# CPU.net
KiCad netlist of a schematic drawn in Altium Designer
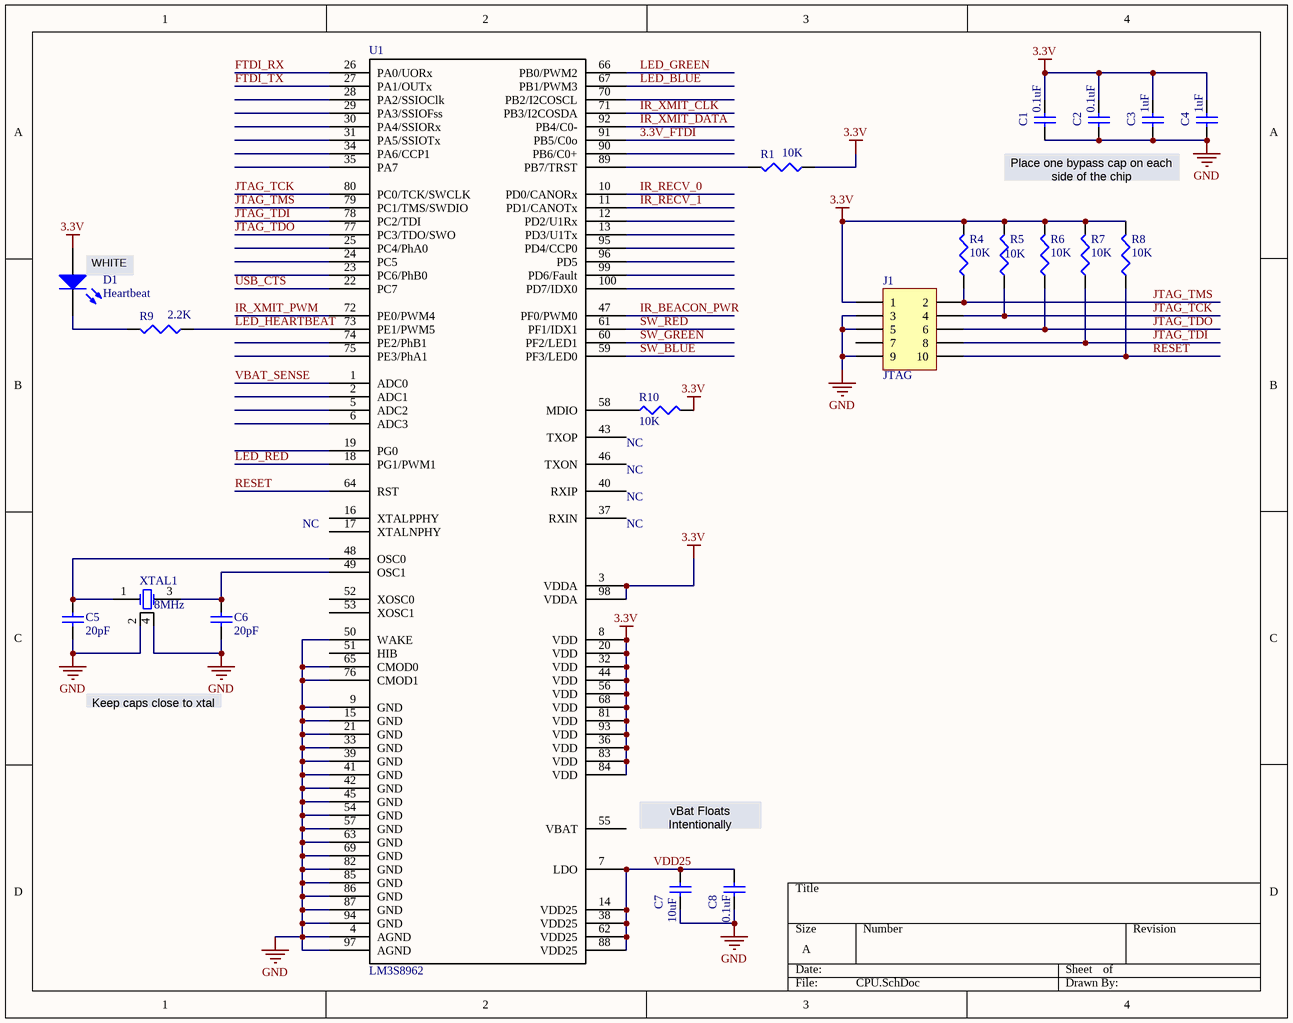
[diagram p0: CPU.SchDoc]

(export (version "E")
  (design (tool "Eeschema 10.0.6"))
  (components
    (comp (ref "C1")
      (value "0.1uF")
      (footprint "0402")
      (description "Capacitor (Semiconductor SIM Model)")
      (fields (field (name "Comment") "Cap Semi") (field (name "PUBLISHER") "Altium Limited"))
      (libsource (lib "Miscellaneous Devices") (part "Cap Semi"))
    )
    (comp (ref "C2")
      (value "0.1uF")
      (footprint "0402")
      (description "Capacitor (Semiconductor SIM Model)")
      (fields (field (name "Comment") "Cap Semi") (field (name "PUBLISHER") "Altium Limited"))
      (libsource (lib "Miscellaneous Devices") (part "Cap Semi"))
    )
    (comp (ref "C3")
      (value "1uF")
      (footprint "1608[0603]")
      (description "Capacitor (Semiconductor SIM Model)")
      (fields (field (name "Comment") "Cap Semi") (field (name "PUBLISHER") "Altium Limited"))
      (libsource (lib "Miscellaneous Devices") (part "Cap Semi"))
    )
    (comp (ref "C4")
      (value "1uF")
      (footprint "1608[0603]")
      (description "Capacitor (Semiconductor SIM Model)")
      (fields (field (name "Comment") "Cap Semi") (field (name "PUBLISHER") "Altium Limited"))
      (libsource (lib "Miscellaneous Devices") (part "Cap Semi"))
    )
    (comp (ref "C5")
      (value "20pF")
      (footprint "0402")
      (description "Capacitor (Semiconductor SIM Model)")
      (fields (field (name "Comment") "Cap Semi") (field (name "PUBLISHER") "Altium Limited"))
      (libsource (lib "Miscellaneous Devices") (part "Cap Semi"))
    )
    (comp (ref "C6")
      (value "20pF")
      (footprint "0402")
      (description "Capacitor (Semiconductor SIM Model)")
      (fields (field (name "Comment") "Cap Semi") (field (name "PUBLISHER") "Altium Limited"))
      (libsource (lib "Miscellaneous Devices") (part "Cap Semi"))
    )
    (comp (ref "C7")
      (value "10uF")
      (footprint "1608[0603]")
      (description "Capacitor (Semiconductor SIM Model)")
      (fields (field (name "Comment") "Cap Semi") (field (name "PUBLISHER") "Altium Limited"))
      (libsource (lib "Miscellaneous Devices") (part "Cap Semi"))
    )
    (comp (ref "C8")
      (value "0.1uF")
      (footprint "0402")
      (description "Capacitor (Semiconductor SIM Model)")
      (fields (field (name "Comment") "Cap Semi") (field (name "PUBLISHER") "Altium Limited"))
      (libsource (lib "Miscellaneous Devices") (part "Cap Semi"))
    )
    (comp (ref "D1")
      (value "Heartbeat")
      (footprint "SurfaceMount(603)")
      (libsource (lib "mrone") (part "LED"))
    )
    (comp (ref "J1")
      (value "JTAG")
      (footprint "JTAG-10")
      (description "Header, 5-Pin, Dual row, Right Angle")
      (fields (field (name "PUBLISHER") "Altium Limited"))
      (libsource (lib "Miscellaneous Connectors") (part "Header 5X2H"))
    )
    (comp (ref "R1")
      (value "10K")
      (footprint "J1-0603")
      (description "Resistor")
      (fields (field (name "Comment") "Res3") (field (name "PUBLISHER") "Altium Limited"))
      (libsource (lib "Miscellaneous Devices") (part "Res3"))
    )
    (comp (ref "R4")
      (value "10K")
      (footprint "J1-0603")
      (description "Resistor")
      (fields (field (name "Comment") "Res3") (field (name "PUBLISHER") "Altium Limited"))
      (libsource (lib "Miscellaneous Devices") (part "Res3"))
    )
    (comp (ref "R5")
      (value "10K")
      (footprint "J1-0603")
      (description "Resistor")
      (fields (field (name "Comment") "Res3") (field (name "PUBLISHER") "Altium Limited"))
      (libsource (lib "Miscellaneous Devices") (part "Res3"))
    )
    (comp (ref "R6")
      (value "10K")
      (footprint "J1-0603")
      (description "Resistor")
      (fields (field (name "Comment") "Res3") (field (name "PUBLISHER") "Altium Limited"))
      (libsource (lib "Miscellaneous Devices") (part "Res3"))
    )
    (comp (ref "R7")
      (value "10K")
      (footprint "J1-0603")
      (description "Resistor")
      (fields (field (name "Comment") "Res3") (field (name "PUBLISHER") "Altium Limited"))
      (libsource (lib "Miscellaneous Devices") (part "Res3"))
    )
    (comp (ref "R8")
      (value "10K")
      (footprint "J1-0603")
      (description "Resistor")
      (fields (field (name "Comment") "Res3") (field (name "PUBLISHER") "Altium Limited"))
      (libsource (lib "Miscellaneous Devices") (part "Res3"))
    )
    (comp (ref "R9")
      (value "2.2K")
      (footprint "J1-0603")
      (description "Resistor")
      (fields (field (name "Comment") "Res3") (field (name "PUBLISHER") "Altium Limited"))
      (libsource (lib "Miscellaneous Devices") (part "Res3"))
    )
    (comp (ref "R10")
      (value "10K")
      (footprint "J1-0603")
      (description "Resistor")
      (fields (field (name "Comment") "Res3") (field (name "PUBLISHER") "Altium Limited"))
      (libsource (lib "Miscellaneous Devices") (part "Res3"))
    )
    (comp (ref "U1")
      (value "LM3S8962")
      (footprint "LQFP-100")
      (libsource (lib "Schematic Components") (part "LM3S8962"))
    )
    (comp (ref "XTAL1") (value "8MHz") (footprint "CRYSTAL") (libsource (lib "mrone") (part "Crystal")))
  )
  (nets
    (net (code "1") (name "/3.3V_FTDI") (class "Default")
      (node (ref "U1") (pin "91") (pinfunction "PB5/C0o_91") (pintype "passive"))
    )
    (net (code "3") (name "/FTDI_RX") (class "Default")
      (node (ref "U1") (pin "26") (pinfunction "PA0/UORx_26") (pintype "passive"))
    )
    (net (code "4") (name "/FTDI_TX") (class "Default")
      (node (ref "U1") (pin "27") (pinfunction "PA1/OUTx_27") (pintype "passive"))
    )
    (net (code "5") (name "/IR_BEACON_PWR") (class "Default")
      (node (ref "U1") (pin "47") (pinfunction "PF0/PWM0_47") (pintype "passive"))
    )
    (net (code "6") (name "/IR_RECV_0") (class "Default")
      (node (ref "U1") (pin "10") (pinfunction "PD0/CANORx_10") (pintype "passive"))
    )
    (net (code "7") (name "/IR_RECV_1") (class "Default")
      (node (ref "U1") (pin "11") (pinfunction "PD1/CANOTx_11") (pintype "passive"))
    )
    (net (code "8") (name "/IR_XMIT_CLK") (class "Default")
      (node (ref "U1") (pin "71") (pinfunction "PB3/I2COSDA_71") (pintype "passive"))
    )
    (net (code "9") (name "/IR_XMIT_DATA") (class "Default")
      (node (ref "U1") (pin "92") (pinfunction "PB4/C0-_92") (pintype "passive"))
    )
    (net (code "10") (name "/IR_XMIT_PWM") (class "Default")
      (node (ref "U1") (pin "72") (pinfunction "PE0/PWM4_72") (pintype "passive"))
    )
    (net (code "11") (name "/JTAG_TCK") (class "Default")
      (node (ref "J1") (pin "4") (pinfunction "4_4") (pintype "passive"))
      (node (ref "R5") (pin "1") (pinfunction "1_1") (pintype "passive"))
      (node (ref "U1") (pin "80") (pinfunction "PC0/TCK/SWCLK_80") (pintype "passive"))
    )
    (net (code "12") (name "/JTAG_TDI") (class "Default")
      (node (ref "J1") (pin "8") (pinfunction "8_8") (pintype "passive"))
      (node (ref "R7") (pin "1") (pinfunction "1_1") (pintype "passive"))
      (node (ref "U1") (pin "78") (pinfunction "PC2/TDI_78") (pintype "passive"))
    )
    (net (code "13") (name "/JTAG_TDO") (class "Default")
      (node (ref "J1") (pin "6") (pinfunction "6_6") (pintype "passive"))
      (node (ref "R6") (pin "1") (pinfunction "1_1") (pintype "passive"))
      (node (ref "U1") (pin "77") (pinfunction "PC3/TDO/SWO_77") (pintype "passive"))
    )
    (net (code "14") (name "/JTAG_TMS") (class "Default")
      (node (ref "J1") (pin "2") (pinfunction "2_2") (pintype "passive"))
      (node (ref "R4") (pin "1") (pinfunction "1_1") (pintype "passive"))
      (node (ref "U1") (pin "79") (pinfunction "PC1/TMS/SWDIO_79") (pintype "passive"))
    )
    (net (code "15") (name "/LED_BLUE") (class "Default")
      (node (ref "U1") (pin "67") (pinfunction "PB1/PWM3_67") (pintype "passive"))
    )
    (net (code "16") (name "/LED_GREEN") (class "Default")
      (node (ref "U1") (pin "66") (pinfunction "PB0/PWM2_66") (pintype "passive"))
    )
    (net (code "17") (name "/LED_HEARTBEAT") (class "Default")
      (node (ref "R9") (pin "1") (pinfunction "1_1") (pintype "passive"))
      (node (ref "U1") (pin "73") (pinfunction "PE1/PWM5_73") (pintype "passive"))
    )
    (net (code "18") (name "/LED_RED") (class "Default")
      (node (ref "U1") (pin "18") (pinfunction "PG1/PWM1_18") (pintype "passive"))
    )
    (net (code "19") (name "/RESET") (class "Default")
      (node (ref "J1") (pin "10") (pinfunction "10_10") (pintype "passive"))
      (node (ref "R8") (pin "1") (pinfunction "1_1") (pintype "passive"))
      (node (ref "U1") (pin "64") (pinfunction "RST_64") (pintype "passive"))
    )
    (net (code "20") (name "/SW_BLUE") (class "Default")
      (node (ref "U1") (pin "59") (pinfunction "PF3/LED0_59") (pintype "passive"))
    )
    (net (code "21") (name "/SW_GREEN") (class "Default")
      (node (ref "U1") (pin "60") (pinfunction "PF2/LED1_60") (pintype "passive"))
    )
    (net (code "22") (name "/SW_RED") (class "Default")
      (node (ref "U1") (pin "61") (pinfunction "PF1/IDX1_61") (pintype "passive"))
    )
    (net (code "23") (name "/USB_CTS") (class "Default")
      (node (ref "U1") (pin "22") (pinfunction "PC7_22") (pintype "passive"))
    )
    (net (code "24") (name "/VBAT_SENSE") (class "Default")
      (node (ref "U1") (pin "1") (pinfunction "ADC0_1") (pintype "passive"))
    )
    (net (code "25") (name "/VDD25") (class "Default")
      (node (ref "C7") (pin "2") (pinfunction "2_2") (pintype "passive"))
      (node (ref "C8") (pin "2") (pinfunction "2_2") (pintype "passive"))
      (node (ref "U1") (pin "14") (pinfunction "VDD25_14") (pintype "passive"))
      (node (ref "U1") (pin "38") (pinfunction "VDD25_38") (pintype "passive"))
      (node (ref "U1") (pin "62") (pinfunction "VDD25_62") (pintype "passive"))
      (node (ref "U1") (pin "7") (pinfunction "LDO_7") (pintype "passive"))
      (node (ref "U1") (pin "88") (pinfunction "VDD25_88") (pintype "passive"))
    )
    (net (code "26") (name "3.3V") (class "Default")
      (node (ref "C1") (pin "2") (pinfunction "2_2") (pintype "passive"))
      (node (ref "C2") (pin "2") (pinfunction "2_2") (pintype "passive"))
      (node (ref "C3") (pin "2") (pinfunction "2_2") (pintype "passive"))
      (node (ref "C4") (pin "2") (pinfunction "2_2") (pintype "passive"))
      (node (ref "D1") (pin "1") (pinfunction "A_1") (pintype "passive"))
      (node (ref "J1") (pin "1") (pinfunction "1_1") (pintype "passive"))
      (node (ref "R1") (pin "1") (pinfunction "1_1") (pintype "passive"))
      (node (ref "R10") (pin "2") (pinfunction "2_2") (pintype "passive"))
      (node (ref "R4") (pin "2") (pinfunction "2_2") (pintype "passive"))
      (node (ref "R5") (pin "2") (pinfunction "2_2") (pintype "passive"))
      (node (ref "R6") (pin "2") (pinfunction "2_2") (pintype "passive"))
      (node (ref "R7") (pin "2") (pinfunction "2_2") (pintype "passive"))
      (node (ref "R8") (pin "2") (pinfunction "2_2") (pintype "passive"))
      (node (ref "U1") (pin "20") (pinfunction "VDD_20") (pintype "passive"))
      (node (ref "U1") (pin "3") (pinfunction "VDDA_3") (pintype "passive"))
      (node (ref "U1") (pin "32") (pinfunction "VDD_32") (pintype "passive"))
      (node (ref "U1") (pin "36") (pinfunction "VDD_36") (pintype "passive"))
      (node (ref "U1") (pin "44") (pinfunction "VDD_44") (pintype "passive"))
      (node (ref "U1") (pin "56") (pinfunction "VDD_56") (pintype "passive"))
      (node (ref "U1") (pin "68") (pinfunction "VDD_68") (pintype "passive"))
      (node (ref "U1") (pin "8") (pinfunction "VDD_8") (pintype "passive"))
      (node (ref "U1") (pin "81") (pinfunction "VDD_81") (pintype "passive"))
      (node (ref "U1") (pin "83") (pinfunction "VDD_83") (pintype "passive"))
      (node (ref "U1") (pin "84") (pinfunction "VDD_84") (pintype "passive"))
      (node (ref "U1") (pin "93") (pinfunction "VDD_93") (pintype "passive"))
      (node (ref "U1") (pin "98") (pinfunction "VDDA_98") (pintype "passive"))
    )
    (net (code "27") (name "GND") (class "Default")
      (node (ref "C1") (pin "1") (pinfunction "1_1") (pintype "passive"))
      (node (ref "C2") (pin "1") (pinfunction "1_1") (pintype "passive"))
      (node (ref "C3") (pin "1") (pinfunction "1_1") (pintype "passive"))
      (node (ref "C4") (pin "1") (pinfunction "1_1") (pintype "passive"))
      (node (ref "C5") (pin "1") (pinfunction "1_1") (pintype "passive"))
      (node (ref "C6") (pin "1") (pinfunction "1_1") (pintype "passive"))
      (node (ref "C7") (pin "1") (pinfunction "1_1") (pintype "passive"))
      (node (ref "C8") (pin "1") (pinfunction "1_1") (pintype "passive"))
      (node (ref "J1") (pin "3") (pinfunction "3_3") (pintype "passive"))
      (node (ref "J1") (pin "5") (pinfunction "5_5") (pintype "passive"))
      (node (ref "J1") (pin "9") (pinfunction "9_9") (pintype "passive"))
      (node (ref "U1") (pin "15") (pinfunction "GND_15") (pintype "passive"))
      (node (ref "U1") (pin "21") (pinfunction "GND_21") (pintype "passive"))
      (node (ref "U1") (pin "33") (pinfunction "GND_33") (pintype "passive"))
      (node (ref "U1") (pin "39") (pinfunction "GND_39") (pintype "passive"))
      (node (ref "U1") (pin "4") (pinfunction "AGND_4") (pintype "passive"))
      (node (ref "U1") (pin "41") (pinfunction "GND_41") (pintype "passive"))
      (node (ref "U1") (pin "42") (pinfunction "GND_42") (pintype "passive"))
      (node (ref "U1") (pin "45") (pinfunction "GND_45") (pintype "passive"))
      (node (ref "U1") (pin "50") (pinfunction "WAKE_50") (pintype "passive"))
      (node (ref "U1") (pin "54") (pinfunction "GND_54") (pintype "passive"))
      (node (ref "U1") (pin "57") (pinfunction "GND_57") (pintype "passive"))
      (node (ref "U1") (pin "63") (pinfunction "GND_63") (pintype "passive"))
      (node (ref "U1") (pin "65") (pinfunction "CMOD0_65") (pintype "passive"))
      (node (ref "U1") (pin "69") (pinfunction "GND_69") (pintype "passive"))
      (node (ref "U1") (pin "76") (pinfunction "CMOD1_76") (pintype "passive"))
      (node (ref "U1") (pin "82") (pinfunction "GND_82") (pintype "passive"))
      (node (ref "U1") (pin "85") (pinfunction "GND_85") (pintype "passive"))
      (node (ref "U1") (pin "86") (pinfunction "GND_86") (pintype "passive"))
      (node (ref "U1") (pin "87") (pinfunction "GND_87") (pintype "passive"))
      (node (ref "U1") (pin "9") (pinfunction "GND_9") (pintype "passive"))
      (node (ref "U1") (pin "94") (pinfunction "GND_94") (pintype "passive"))
      (node (ref "U1") (pin "97") (pinfunction "AGND_97") (pintype "passive"))
      (node (ref "XTAL1") (pin "2") (pinfunction "GND_2") (pintype "passive"))
      (node (ref "XTAL1") (pin "4") (pinfunction "GND_4") (pintype "passive"))
    )
    (net (code "28") (name "Net-(D1-K)") (class "Default")
      (node (ref "D1") (pin "2") (pinfunction "K_2") (pintype "passive"))
      (node (ref "R9") (pin "2") (pinfunction "2_2") (pintype "passive"))
    )
    (net (code "29") (name "Net-(U1-MDIO)") (class "Default")
      (node (ref "R10") (pin "1") (pinfunction "1_1") (pintype "passive"))
      (node (ref "U1") (pin "58") (pinfunction "MDIO_58") (pintype "passive"))
    )
    (net (code "30") (name "Net-(U1-OSC0)") (class "Default")
      (node (ref "C5") (pin "2") (pinfunction "2_2") (pintype "passive"))
      (node (ref "U1") (pin "48") (pinfunction "OSC0_48") (pintype "passive"))
      (node (ref "XTAL1") (pin "1") (pinfunction "OSC1_1") (pintype "passive"))
    )
    (net (code "31") (name "Net-(U1-OSC1)") (class "Default")
      (node (ref "C6") (pin "2") (pinfunction "2_2") (pintype "passive"))
      (node (ref "U1") (pin "49") (pinfunction "OSC1_49") (pintype "passive"))
      (node (ref "XTAL1") (pin "3") (pinfunction "OSC2_3") (pintype "passive"))
    )
    (net (code "32") (name "Net-(U1-PB7{slash}TRST)") (class "Default")
      (node (ref "R1") (pin "2") (pinfunction "2_2") (pintype "passive"))
      (node (ref "U1") (pin "89") (pinfunction "PB7/TRST_89") (pintype "passive"))
    )
    (net (code "33") (name "unconnected-(J1-Pad7)") (class "Default")
      (node (ref "J1") (pin "7") (pinfunction "7_7") (pintype "passive"))
    )
    (net (code "34") (name "unconnected-(U1-ADC1-Pad2)") (class "Default")
      (node (ref "U1") (pin "2") (pinfunction "ADC1_2") (pintype "passive"))
    )
    (net (code "35") (name "unconnected-(U1-ADC2-Pad5)") (class "Default")
      (node (ref "U1") (pin "5") (pinfunction "ADC2_5") (pintype "passive"))
    )
    (net (code "36") (name "unconnected-(U1-ADC3-Pad6)") (class "Default")
      (node (ref "U1") (pin "6") (pinfunction "ADC3_6") (pintype "passive"))
    )
    (net (code "37") (name "unconnected-(U1-HIB-Pad51)") (class "Default")
      (node (ref "U1") (pin "51") (pinfunction "HIB_51") (pintype "passive"))
    )
    (net (code "38") (name "unconnected-(U1-PA2{slash}SSIOClk-Pad28)") (class "Default")
      (node (ref "U1") (pin "28") (pinfunction "PA2/SSIOClk_28") (pintype "passive"))
    )
    (net (code "39") (name "unconnected-(U1-PA3{slash}SSIOFss-Pad29)") (class "Default")
      (node (ref "U1") (pin "29") (pinfunction "PA3/SSIOFss_29") (pintype "passive"))
    )
    (net (code "40") (name "unconnected-(U1-PA4{slash}SSIORx-Pad30)") (class "Default")
      (node (ref "U1") (pin "30") (pinfunction "PA4/SSIORx_30") (pintype "passive"))
    )
    (net (code "41") (name "unconnected-(U1-PA5{slash}SSIOTx-Pad31)") (class "Default")
      (node (ref "U1") (pin "31") (pinfunction "PA5/SSIOTx_31") (pintype "passive"))
    )
    (net (code "42") (name "unconnected-(U1-PA6{slash}CCP1-Pad34)") (class "Default")
      (node (ref "U1") (pin "34") (pinfunction "PA6/CCP1_34") (pintype "passive"))
    )
    (net (code "43") (name "unconnected-(U1-PA7-Pad35)") (class "Default")
      (node (ref "U1") (pin "35") (pinfunction "PA7_35") (pintype "passive"))
    )
    (net (code "44") (name "unconnected-(U1-PB2{slash}I2COSCL-Pad70)") (class "Default")
      (node (ref "U1") (pin "70") (pinfunction "PB2/I2COSCL_70") (pintype "passive"))
    )
    (net (code "45") (name "unconnected-(U1-PB6{slash}C0+-Pad90)") (class "Default")
      (node (ref "U1") (pin "90") (pinfunction "PB6/C0+_90") (pintype "passive"))
    )
    (net (code "46") (name "unconnected-(U1-PC4{slash}PhA0-Pad25)") (class "Default")
      (node (ref "U1") (pin "25") (pinfunction "PC4/PhA0_25") (pintype "passive"))
    )
    (net (code "47") (name "unconnected-(U1-PC5-Pad24)") (class "Default")
      (node (ref "U1") (pin "24") (pinfunction "PC5_24") (pintype "passive"))
    )
    (net (code "48") (name "unconnected-(U1-PC6{slash}PhB0-Pad23)") (class "Default")
      (node (ref "U1") (pin "23") (pinfunction "PC6/PhB0_23") (pintype "passive"))
    )
    (net (code "49") (name "unconnected-(U1-PD2{slash}U1Rx-Pad12)") (class "Default")
      (node (ref "U1") (pin "12") (pinfunction "PD2/U1Rx_12") (pintype "passive"))
    )
    (net (code "50") (name "unconnected-(U1-PD3{slash}U1Tx-Pad13)") (class "Default")
      (node (ref "U1") (pin "13") (pinfunction "PD3/U1Tx_13") (pintype "passive"))
    )
    (net (code "51") (name "unconnected-(U1-PD4{slash}CCP0-Pad95)") (class "Default")
      (node (ref "U1") (pin "95") (pinfunction "PD4/CCP0_95") (pintype "passive"))
    )
    (net (code "52") (name "unconnected-(U1-PD5-Pad96)") (class "Default")
      (node (ref "U1") (pin "96") (pinfunction "PD5_96") (pintype "passive"))
    )
    (net (code "53") (name "unconnected-(U1-PD6{slash}Fault-Pad99)") (class "Default")
      (node (ref "U1") (pin "99") (pinfunction "PD6/Fault_99") (pintype "passive"))
    )
    (net (code "54") (name "unconnected-(U1-PD7{slash}IDX0-Pad100)") (class "Default")
      (node (ref "U1") (pin "100") (pinfunction "PD7/IDX0_100") (pintype "passive"))
    )
    (net (code "55") (name "unconnected-(U1-PE2{slash}PhB1-Pad74)") (class "Default")
      (node (ref "U1") (pin "74") (pinfunction "PE2/PhB1_74") (pintype "passive"))
    )
    (net (code "56") (name "unconnected-(U1-PE3{slash}PhA1-Pad75)") (class "Default")
      (node (ref "U1") (pin "75") (pinfunction "PE3/PhA1_75") (pintype "passive"))
    )
    (net (code "57") (name "unconnected-(U1-PG0-Pad19)") (class "Default")
      (node (ref "U1") (pin "19") (pinfunction "PG0_19") (pintype "passive"))
    )
    (net (code "58") (name "unconnected-(U1-RXIN-Pad37)") (class "Default")
      (node (ref "U1") (pin "37") (pinfunction "RXIN_37") (pintype "passive"))
    )
    (net (code "59") (name "unconnected-(U1-RXIP-Pad40)") (class "Default")
      (node (ref "U1") (pin "40") (pinfunction "RXIP_40") (pintype "passive"))
    )
    (net (code "60") (name "unconnected-(U1-TXON-Pad46)") (class "Default")
      (node (ref "U1") (pin "46") (pinfunction "TXON_46") (pintype "passive"))
    )
    (net (code "61") (name "unconnected-(U1-TXOP-Pad43)") (class "Default")
      (node (ref "U1") (pin "43") (pinfunction "TXOP_43") (pintype "passive"))
    )
    (net (code "62") (name "unconnected-(U1-VBAT-Pad55)") (class "Default")
      (node (ref "U1") (pin "55") (pinfunction "VBAT_55") (pintype "passive"))
    )
    (net (code "63") (name "unconnected-(U1-XOSC0-Pad52)") (class "Default")
      (node (ref "U1") (pin "52") (pinfunction "XOSC0_52") (pintype "passive"))
    )
    (net (code "64") (name "unconnected-(U1-XOSC1-Pad53)") (class "Default")
      (node (ref "U1") (pin "53") (pinfunction "XOSC1_53") (pintype "passive"))
    )
    (net (code "65") (name "unconnected-(U1-XTALNPHY-Pad17)") (class "Default")
      (node (ref "U1") (pin "17") (pinfunction "XTALNPHY_17") (pintype "passive"))
    )
    (net (code "66") (name "unconnected-(U1-XTALPPHY-Pad16)") (class "Default")
      (node (ref "U1") (pin "16") (pinfunction "XTALPPHY_16") (pintype "passive"))
    )
  )
)
